# UBC-Thunderbots_PCB_Power__archive_power.net
KiCad netlist of a schematic drawn in Altium Designer
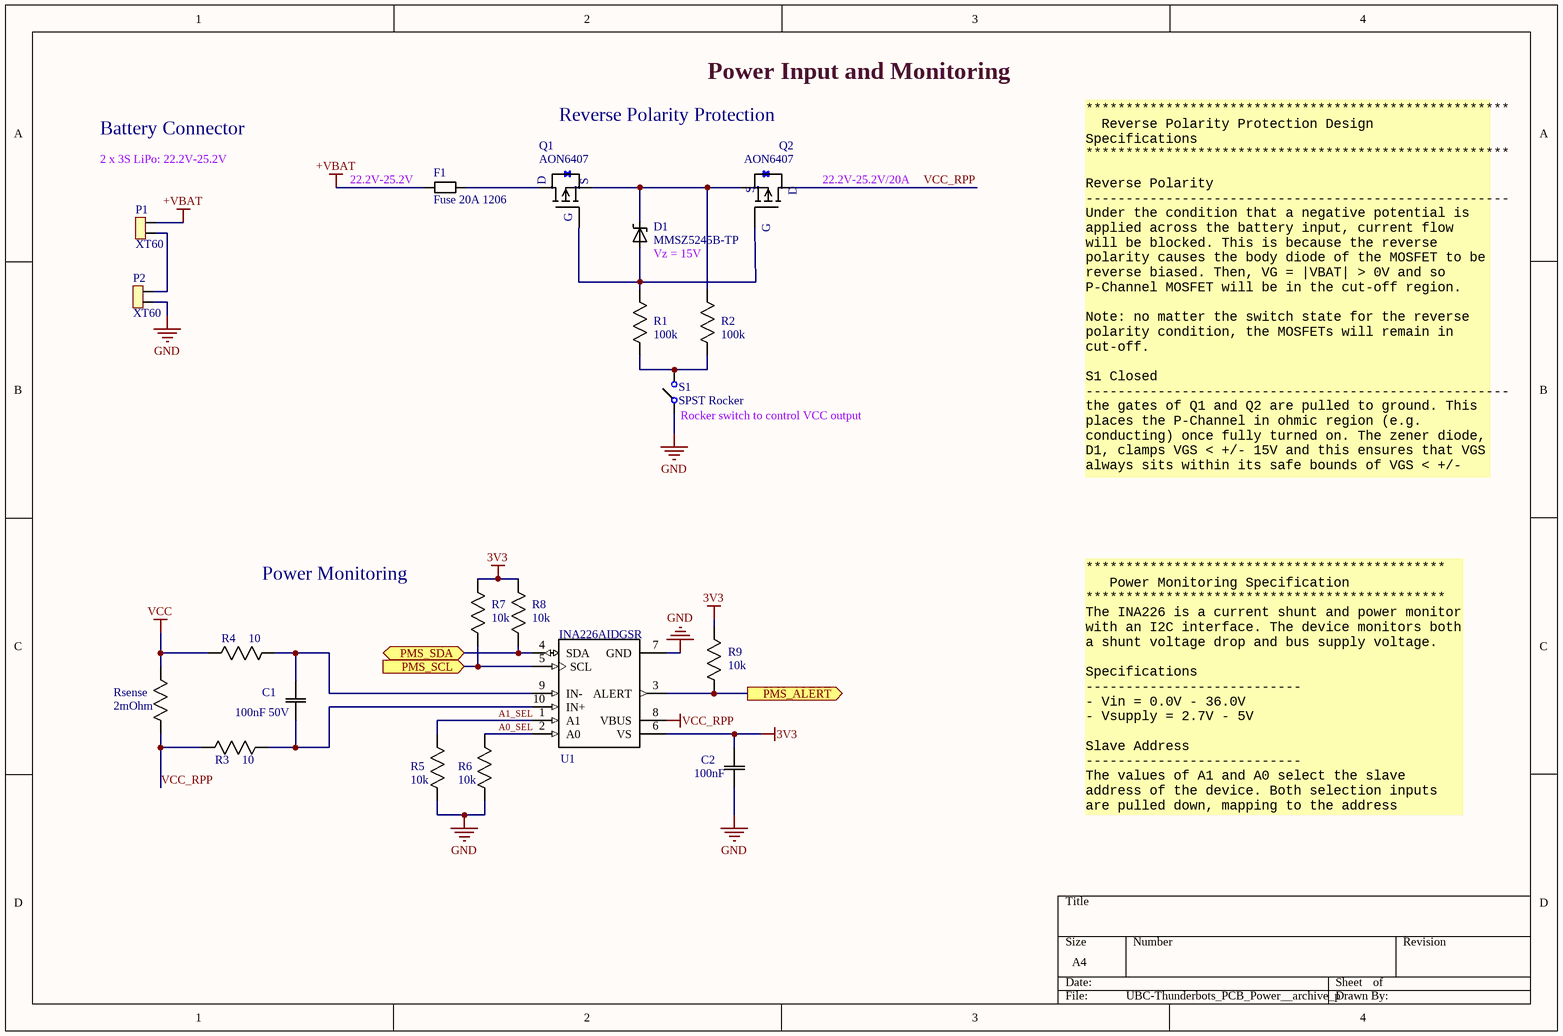
[diagram p0: UBC-Thunderbots_PCB_Power__archive_power-v2.2_pcb__power-input.SchDoc]

(export (version "E")
  (design (tool "Eeschema 10.0.6"))
  (components
    (comp (ref "C1")
      (value "100nF 50V")
      (footprint "0805")
      (description "CAP CER 0.1UF 50V X7R 0805")
      (fields (field (name "MP") "CC0805KRX7R9BB104") (field (name "MF") "Yageo"))
      (libsource (lib "AltiumLibraries") (part "CAP 100nF 0805"))
    )
    (comp (ref "C2")
      (value "100nF")
      (footprint "0805")
      (description "CAP CER 0.1UF 50V X7R 0805")
      (fields (field (name "MP") "CC0805KRX7R9BB104") (field (name "MF") "Yageo"))
      (libsource (lib "AltiumLibraries") (part "CAP 100nF 0805"))
    )
    (comp (ref "D1")
      (value "MMSZ5245B-TP")
      (footprint "SOD-123")
      (description "Zener Diode 15V 500mW ±5% Surface Mount SOD-123")
      (fields (field (name "MP") "MMSZ5224BT1G") (field (name "MF") "ON Semiconductor"))
      (libsource (lib "AltiumLibraries") (part "MMSZ5245B-TP"))
    )
    (comp (ref "F1")
      (value "Fuse 20A 1206")
      (footprint "1206")
      (description "FUSE BOARD MOUNT 20A 32VAC 63VDC")
      (fields (field (name "MF") "Schurter Inc.") (field (name "MP") "3413.0331.22"))
      (libsource (lib "AltiumLibraries") (part "Fuse 20A 1206"))
    )
    (comp (ref "P1")
      (value "XT60")
      (footprint "XT60Connector")
      (description "XT60 CONNECTORS FEMALE PAIR")
      (fields (field (name "MF") "SparkFun Electronics") (field (name "MP") "PRT-10474"))
      (libsource (lib "AltiumLibraries") (part "XT60 Connector"))
    )
    (comp (ref "P2")
      (value "XT60")
      (footprint "XT60Connector")
      (description "XT60 CONNECTORS FEMALE PAIR")
      (fields (field (name "MF") "SparkFun Electronics") (field (name "MP") "PRT-10474"))
      (libsource (lib "AltiumLibraries") (part "XT60 Connector"))
    )
    (comp (ref "Q1")
      (value "AON6407")
      (footprint "8-PowerSMD")
      (description "P-Channel 30V 32A (Ta), 85A (Tc) 7.3W (Ta), 83W (Tc) Surface Mount 8-DFN (5x6)")
      (fields (field (name "MF") "Alpha & Omega Semiconductor Inc."))
      (libsource (lib "AltiumLibraries") (part "AON6407"))
    )
    (comp (ref "Q2")
      (value "AON6407")
      (footprint "8-PowerSMD")
      (description "P-Channel 30V 32A (Ta), 85A (Tc) 7.3W (Ta), 83W (Tc) Surface Mount 8-DFN (5x6)")
      (fields (field (name "MF") "Alpha & Omega Semiconductor Inc."))
      (libsource (lib "AltiumLibraries") (part "AON6407"))
    )
    (comp (ref "R1")
      (value "100k")
      (footprint "0805")
      (description "RES SMD 100K OHM 1% 1/8W 0805")
      (fields (field (name "MP") "RC0805FR-07100KL") (field (name "MF") "Yageo"))
      (libsource (lib "AltiumLibraries") (part "RES 100k 0805"))
    )
    (comp (ref "R2")
      (value "100k")
      (footprint "0805")
      (description "RES SMD 100K OHM 1% 1/8W 0805")
      (fields (field (name "MP") "RC0805FR-07100KL") (field (name "MF") "Yageo"))
      (libsource (lib "AltiumLibraries") (part "RES 100k 0805"))
    )
    (comp (ref "R3")
      (value "10")
      (footprint "0805")
      (description "RES SMD 10 OHM 1% 1/8W 0805")
      (fields (field (name "MP") "RC0805FR-0710RL") (field (name "MF") "Yageo"))
      (libsource (lib "AltiumLibraries") (part "RES 10 0805"))
    )
    (comp (ref "R4")
      (value "10")
      (footprint "0805")
      (description "RES SMD 10 OHM 1% 1/8W 0805")
      (fields (field (name "MP") "RC0805FR-0710RL") (field (name "MF") "Yageo"))
      (libsource (lib "AltiumLibraries") (part "RES 10 0805"))
    )
    (comp (ref "R5")
      (value "10k")
      (footprint "0805")
      (description "RES SMD 10K OHM 1% 1/8W 0805")
      (fields (field (name "TOLERANCE") "1%"))
      (libsource (lib "AltiumLibraries") (part "RES 10k 1/8W"))
    )
    (comp (ref "R6")
      (value "10k")
      (footprint "0805")
      (description "RES SMD 10K OHM 1% 1/8W 0805")
      (fields (field (name "TOLERANCE") "1%"))
      (libsource (lib "AltiumLibraries") (part "RES 10k 1/8W"))
    )
    (comp (ref "R7")
      (value "10k")
      (footprint "0805")
      (description "RES SMD 10K OHM 1% 1/8W 0805")
      (fields (field (name "MP") "RC0805FR-0710KL") (field (name "MF") "Yageo"))
      (libsource (lib "AltiumLibraries") (part "RES 10k 0805"))
    )
    (comp (ref "R8")
      (value "10k")
      (footprint "0805")
      (description "RES SMD 10K OHM 1% 1/8W 0805")
      (fields (field (name "MP") "RC0805FR-0710KL") (field (name "MF") "Yageo"))
      (libsource (lib "AltiumLibraries") (part "RES 10k 0805"))
    )
    (comp (ref "R9")
      (value "10k")
      (footprint "0805")
      (description "RES SMD 10K OHM 1% 1/8W 0805")
      (fields (field (name "MP") "RC0805FR-0710KL") (field (name "MF") "Yageo"))
      (libsource (lib "AltiumLibraries") (part "RES 10k 0805"))
    )
    (comp (ref "Rsense")
      (value "2mOhm")
      (footprint "1206")
      (description "RES 0.002 OHM 1% 1W 1206")
      (fields (field (name "MP") "CSR1206-0R002F1") (field (name "MF") "Riedon"))
      (libsource (lib "AltiumLibraries") (part "RES 2mOhm 1206"))
    )
    (comp (ref "S1")
      (value "SPST Rocker")
      (footprint "SWITCH ROCKER SPST 10A 125V")
      (description "Rocker Switch SPST 10A (AC) 125V Panel Mount, Snap-In")
      (fields (field (name "MP") "SRB22A2FBBNN") (field (name "MF") "ZF Electronics"))
      (libsource (lib "AltiumLibraries") (part "SWITCH ROCKER SPST 10A 125V"))
    )
    (comp (ref "U1")
      (value "INA226AIDGSR")
      (footprint "10-VSSOP")
      (fields (field (name "MF") "Texas Instruments"))
      (libsource (lib "AltiumLibraries") (part "INA226AIDGSR"))
    )
  )
  (nets
    (net (code "1") (name "+VBAT") (class "Default")
      (node (ref "F1") (pin "1") (pinfunction "1_1") (pintype "passive"))
      (node (ref "P1") (pin "2") (pinfunction "2_2") (pintype "passive"))
    )
    (net (code "2") (name "/A0_SEL") (class "Default")
      (node (ref "R6") (pin "1") (pinfunction "R1_1") (pintype "passive"))
      (node (ref "U1") (pin "2") (pinfunction "A0_2") (pintype "input"))
    )
    (net (code "3") (name "/A1_SEL") (class "Default")
      (node (ref "R5") (pin "1") (pinfunction "R1_1") (pintype "passive"))
      (node (ref "U1") (pin "1") (pinfunction "A1_1") (pintype "input"))
    )
    (net (code "4") (name "/PMS_ALERT") (class "Default")
      (node (ref "R9") (pin "2") (pinfunction "R2_2") (pintype "passive"))
      (node (ref "U1") (pin "3") (pinfunction "ALERT_3") (pintype "output"))
    )
    (net (code "5") (name "/PMS_SCL") (class "Default")
      (node (ref "R7") (pin "2") (pinfunction "R2_2") (pintype "passive"))
      (node (ref "U1") (pin "5") (pinfunction "SCL_5") (pintype "input"))
    )
    (net (code "6") (name "/PMS_SDA") (class "Default")
      (node (ref "R8") (pin "2") (pinfunction "R2_2") (pintype "passive"))
      (node (ref "U1") (pin "4") (pinfunction "SDA_4") (pintype "bidirectional"))
    )
    (net (code "7") (name "3V3") (class "Default")
      (node (ref "C2") (pin "2") (pinfunction "C2_2") (pintype "passive"))
      (node (ref "R7") (pin "1") (pinfunction "R1_1") (pintype "passive"))
      (node (ref "R8") (pin "1") (pinfunction "R1_1") (pintype "passive"))
      (node (ref "R9") (pin "1") (pinfunction "R1_1") (pintype "passive"))
      (node (ref "U1") (pin "6") (pinfunction "VS_6") (pintype "power_in"))
    )
    (net (code "8") (name "GND") (class "Default")
      (node (ref "C2") (pin "1") (pinfunction "C1_1") (pintype "passive"))
      (node (ref "P2") (pin "1") (pinfunction "1_1") (pintype "passive"))
      (node (ref "R5") (pin "2") (pinfunction "R2_2") (pintype "passive"))
      (node (ref "R6") (pin "2") (pinfunction "R2_2") (pintype "passive"))
      (node (ref "S1") (pin "0") (pinfunction "0_0") (pintype "passive"))
      (node (ref "U1") (pin "7") (pinfunction "GND_7") (pintype "power_in"))
    )
    (net (code "9") (name "Net-(C1-C1)") (class "Default")
      (node (ref "C1") (pin "1") (pinfunction "C1_1") (pintype "passive"))
      (node (ref "R3") (pin "1") (pinfunction "R1_1") (pintype "passive"))
      (node (ref "U1") (pin "10") (pinfunction "IN+_10") (pintype "input"))
    )
    (net (code "10") (name "Net-(C1-C2)") (class "Default")
      (node (ref "C1") (pin "2") (pinfunction "C2_2") (pintype "passive"))
      (node (ref "R4") (pin "1") (pinfunction "R1_1") (pintype "passive"))
      (node (ref "U1") (pin "9") (pinfunction "IN-_9") (pintype "input"))
    )
    (net (code "11") (name "Net-(F1-Pad2)") (class "Default")
      (node (ref "F1") (pin "2") (pinfunction "2_2") (pintype "passive"))
      (node (ref "Q1") (pin "D") (pinfunction "D_D") (pintype "passive"))
    )
    (net (code "12") (name "Net-(P1-Pad1)") (class "Default")
      (node (ref "P1") (pin "1") (pinfunction "1_1") (pintype "passive"))
      (node (ref "P2") (pin "2") (pinfunction "2_2") (pintype "passive"))
    )
    (net (code "13") (name "Net-(R1-R1)") (class "Default")
      (node (ref "D1") (pin "A") (pinfunction "A_A") (pintype "passive"))
      (node (ref "Q1") (pin "G") (pinfunction "G_G") (pintype "passive"))
      (node (ref "Q2") (pin "G") (pinfunction "G_G") (pintype "passive"))
      (node (ref "R1") (pin "1") (pinfunction "R1_1") (pintype "passive"))
    )
    (net (code "14") (name "Net-(R1-R2)") (class "Default")
      (node (ref "R1") (pin "2") (pinfunction "R2_2") (pintype "passive"))
      (node (ref "R2") (pin "2") (pinfunction "R2_2") (pintype "passive"))
      (node (ref "S1") (pin "1") (pinfunction "1_1") (pintype "passive"))
    )
    (net (code "15") (name "Net-(R2-R1)") (class "Default")
      (node (ref "D1") (pin "C") (pinfunction "C_C") (pintype "passive"))
      (node (ref "Q1") (pin "S") (pinfunction "S_S") (pintype "passive"))
      (node (ref "Q2") (pin "S") (pinfunction "S_S") (pintype "passive"))
      (node (ref "R2") (pin "1") (pinfunction "R1_1") (pintype "passive"))
    )
    (net (code "16") (name "VCC") (class "Default")
      (node (ref "R4") (pin "2") (pinfunction "R2_2") (pintype "passive"))
      (node (ref "Rsense") (pin "1") (pinfunction "R1_1") (pintype "passive"))
    )
    (net (code "17") (name "VCC_RPP") (class "Default")
      (node (ref "Q2") (pin "D") (pinfunction "D_D") (pintype "passive"))
      (node (ref "R3") (pin "2") (pinfunction "R2_2") (pintype "passive"))
      (node (ref "Rsense") (pin "2") (pinfunction "R2_2") (pintype "passive"))
      (node (ref "U1") (pin "8") (pinfunction "VBUS_8") (pintype "power_in"))
    )
  )
)
